# Sensors-V1.net
KiCad netlist of a schematic drawn in EAGLE
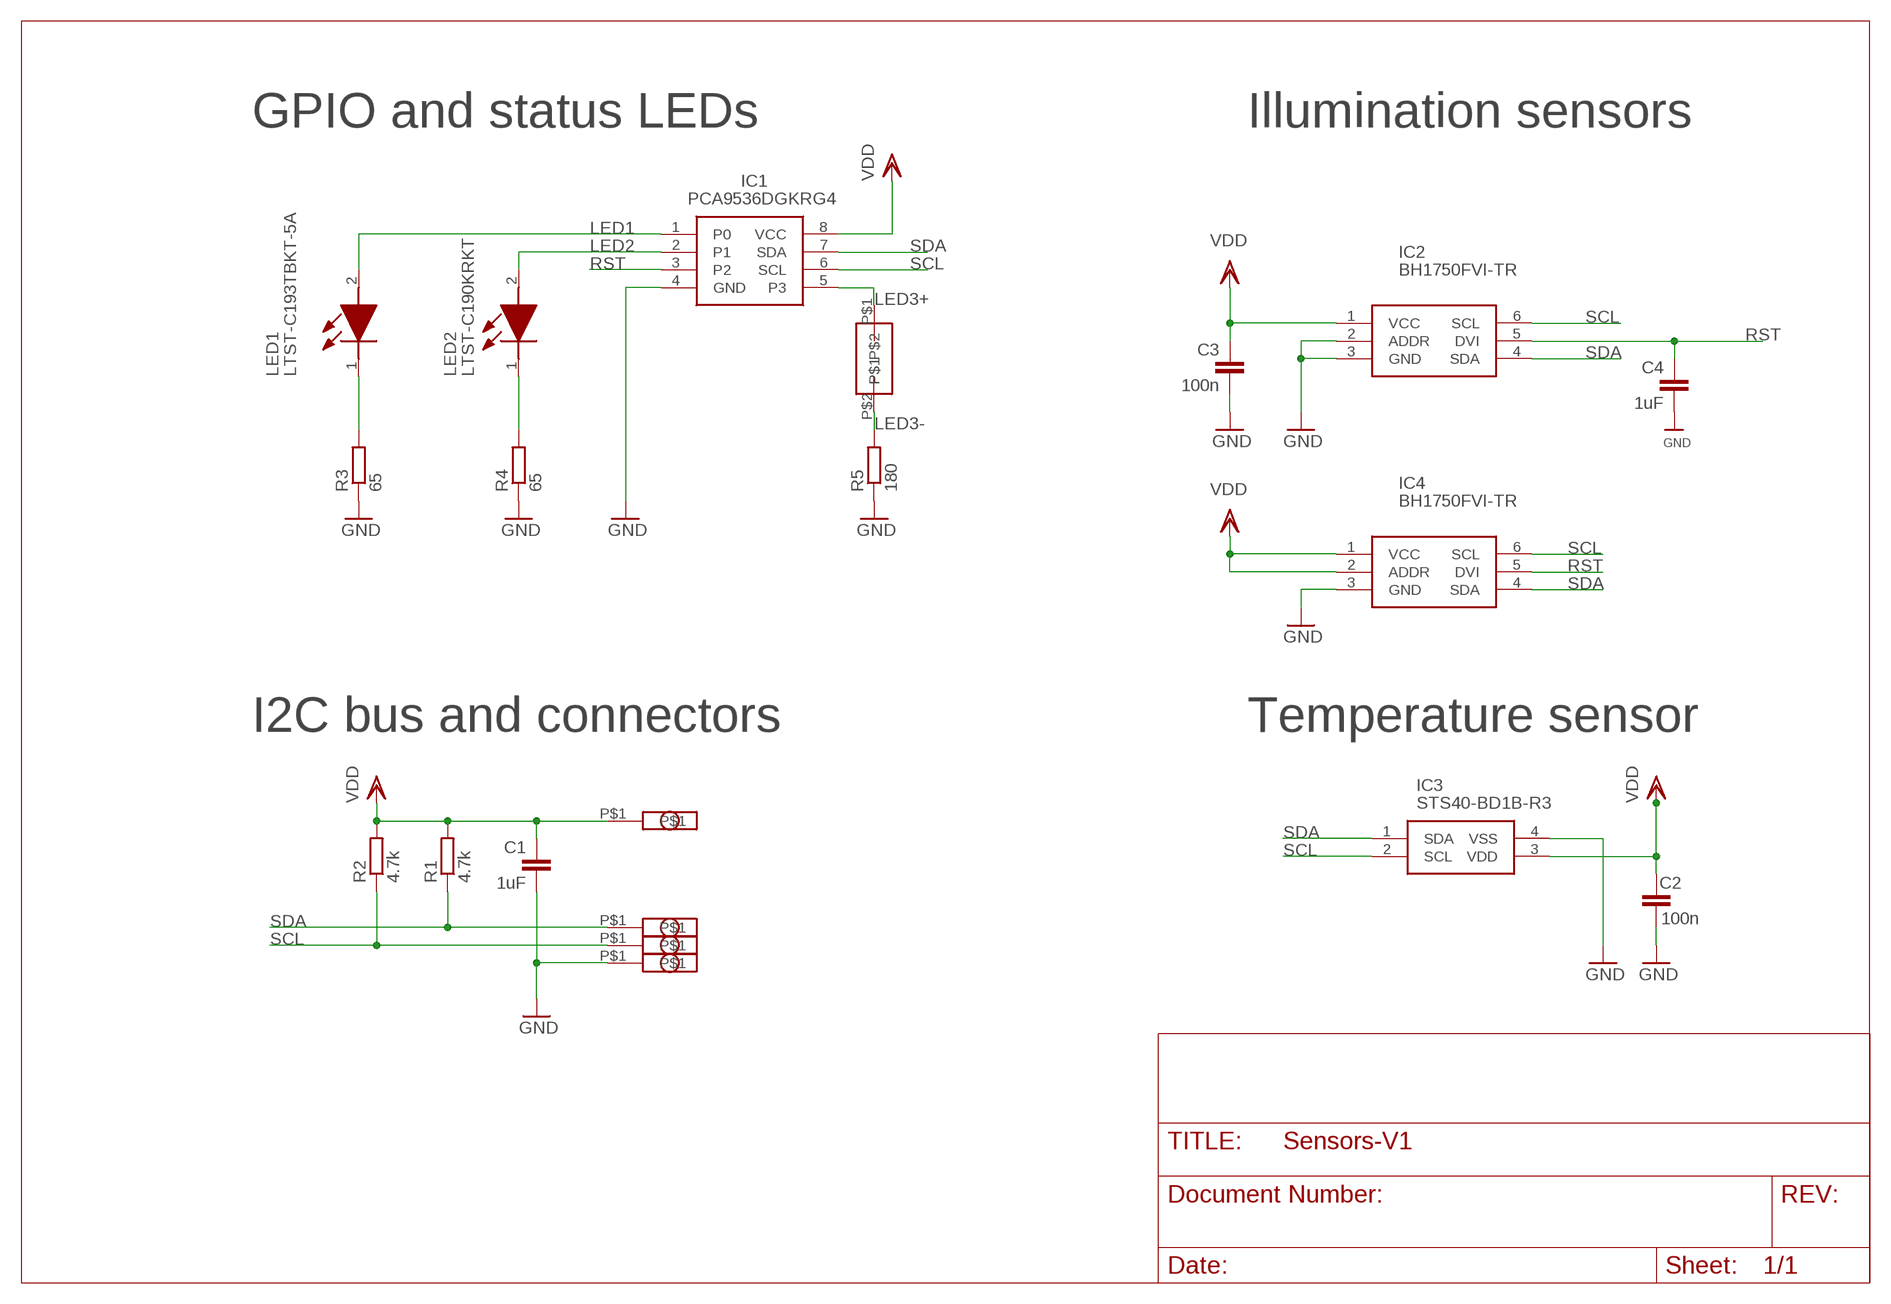
[diagram p0: schematic, sheet 1]

(export (version "E")
  (design (tool "Eeschema 10.0.6"))
  (components
    (comp (ref "C1")
      (value "1uF")
      (footprint "eagle-import:C0603")
      (libsource (lib "eagle-import") (part "C-EUC0603"))
    )
    (comp (ref "C2")
      (value "100n")
      (footprint "eagle-import:C0603")
      (libsource (lib "eagle-import") (part "C-EUC0603"))
    )
    (comp (ref "C3")
      (value "100n")
      (footprint "eagle-import:C0603")
      (libsource (lib "eagle-import") (part "C-EUC0603"))
    )
    (comp (ref "C4")
      (value "1uF")
      (footprint "eagle-import:C0603")
      (libsource (lib "eagle-import") (part "C-EUC0603"))
    )
    (comp (ref "IC1")
      (value "PCA9536DGKRG4")
      (footprint "eagle-import:SOP65P490X110-8N")
      (fields (field (name "MOUSER_PART_NUMBER") "595-PCA9536DGKRG4"))
      (libsource (lib "eagle-import") (part "PCA9536DGKRG4"))
    )
    (comp (ref "IC2")
      (value "BH1750FVI-TR")
      (footprint "eagle-import:WSOF6")
      (libsource (lib "eagle-import") (part "BH1750FVI-TR"))
    )
    (comp (ref "IC3")
      (value "STS40-BD1B-R3")
      (footprint "eagle-import:STS40BD1BR3")
      (fields (field (name "MOUSER_PART_NUMBER") "403-STS40-BD1B-R3"))
      (libsource (lib "eagle-import") (part "STS40-BD1B-R3"))
    )
    (comp (ref "IC4")
      (value "BH1750FVI-TR")
      (footprint "eagle-import:WSOF6")
      (libsource (lib "eagle-import") (part "BH1750FVI-TR"))
    )
    (comp (ref "LED1")
      (value "LTST-C193TBKT-5A")
      (footprint "eagle-import:LEDC1608X45N")
      (fields (field (name "MOUSER_PART_NUMBER") "859-LTSTC193TBKT5A"))
      (libsource (lib "eagle-import") (part "LTST-C193TBKT-5A"))
    )
    (comp (ref "LED2")
      (value "LTST-C190KRKT")
      (footprint "eagle-import:LEDC1607X80N")
      (fields
        (field (name "MANUFACTURER_PART_NUMBER") "LTST-C190KFKT")
        (field (name "MOUSER_PART_NUMBER") "859-LTST-C190KFKT")
      )
      (libsource (lib "eagle-import") (part "LTST-C190KFKT"))
    )
    (comp (ref "R1")
      (value "4.7k")
      (footprint "eagle-import:R0603")
      (libsource (lib "eagle-import") (part "R_JLMR0603"))
    )
    (comp (ref "R2")
      (value "4.7k")
      (footprint "eagle-import:R0603")
      (libsource (lib "eagle-import") (part "R_JLMR0603"))
    )
    (comp (ref "R3")
      (value "65")
      (footprint "eagle-import:R0603")
      (libsource (lib "eagle-import") (part "R_JLMR0603"))
    )
    (comp (ref "R4")
      (value "65")
      (footprint "eagle-import:R0603")
      (libsource (lib "eagle-import") (part "R_JLMR0603"))
    )
    (comp (ref "R5")
      (value "180")
      (footprint "eagle-import:R0603")
      (libsource (lib "eagle-import") (part "R_JLMR0603"))
    )
    (comp (ref "U$1")
      (value "PAD")
      (footprint "eagle-import:PAD-15")
      (libsource (lib "eagle-import") (part "PAD"))
    )
    (comp (ref "U$2")
      (value "PAD")
      (footprint "eagle-import:PAD-15")
      (libsource (lib "eagle-import") (part "PAD"))
    )
    (comp (ref "U$3")
      (value "PAD")
      (footprint "eagle-import:PAD-15")
      (libsource (lib "eagle-import") (part "PAD"))
    )
    (comp (ref "U$4")
      (value "PAD")
      (footprint "eagle-import:PAD-15")
      (libsource (lib "eagle-import") (part "PAD"))
    )
    (comp (ref "U$5")
      (value "LEDPINS")
      (footprint "eagle-import:LEDPINS254")
      (libsource (lib "eagle-import") (part "LEDPINS"))
    )
  )
  (nets
    (net (code "1") (name "/LED1") (class "Default")
      (node (ref "IC1") (pin "1") (pinfunction "P0_1") (pintype "bidirectional"))
      (node (ref "LED1") (pin "2") (pinfunction "A_2") (pintype "bidirectional"))
    )
    (net (code "2") (name "/LED2") (class "Default")
      (node (ref "IC1") (pin "2") (pinfunction "P1_2") (pintype "bidirectional"))
      (node (ref "LED2") (pin "2") (pinfunction "A_2") (pintype "bidirectional"))
    )
    (net (code "3") (name "/LED3+") (class "Default")
      (node (ref "IC1") (pin "5") (pinfunction "P3_5") (pintype "bidirectional"))
      (node (ref "U$5") (pin "P$1") (pinfunction "P$1_P$1") (pintype "bidirectional"))
    )
    (net (code "4") (name "/LED3-") (class "Default")
      (node (ref "R5") (pin "2") (pinfunction "2_2") (pintype "passive"))
      (node (ref "U$5") (pin "P$2") (pinfunction "P$2_P$2") (pintype "bidirectional"))
    )
    (net (code "5") (name "/RST") (class "Default")
      (node (ref "C4") (pin "1") (pinfunction "1_1") (pintype "passive"))
      (node (ref "IC1") (pin "3") (pinfunction "P2_3") (pintype "bidirectional"))
      (node (ref "IC2") (pin "5") (pinfunction "DVI_5") (pintype "bidirectional"))
      (node (ref "IC4") (pin "5") (pinfunction "DVI_5") (pintype "bidirectional"))
    )
    (net (code "6") (name "/SCL") (class "Default")
      (node (ref "IC1") (pin "6") (pinfunction "SCL_6") (pintype "bidirectional"))
      (node (ref "IC2") (pin "6") (pinfunction "SCL_6") (pintype "bidirectional"))
      (node (ref "IC3") (pin "2") (pinfunction "SCL_2") (pintype "bidirectional"))
      (node (ref "IC4") (pin "6") (pinfunction "SCL_6") (pintype "bidirectional"))
      (node (ref "R2") (pin "1") (pinfunction "1_1") (pintype "passive"))
      (node (ref "U$2") (pin "P$1") (pinfunction "P$1_P$1") (pintype "bidirectional"))
    )
    (net (code "7") (name "/SDA") (class "Default")
      (node (ref "IC1") (pin "7") (pinfunction "SDA_7") (pintype "bidirectional"))
      (node (ref "IC2") (pin "4") (pinfunction "SDA_4") (pintype "bidirectional"))
      (node (ref "IC3") (pin "1") (pinfunction "SDA_1") (pintype "bidirectional"))
      (node (ref "IC4") (pin "4") (pinfunction "SDA_4") (pintype "bidirectional"))
      (node (ref "R1") (pin "1") (pinfunction "1_1") (pintype "passive"))
      (node (ref "U$1") (pin "P$1") (pinfunction "P$1_P$1") (pintype "bidirectional"))
    )
    (net (code "8") (name "GND") (class "Default")
      (node (ref "C1") (pin "2") (pinfunction "2_2") (pintype "passive"))
      (node (ref "C2") (pin "2") (pinfunction "2_2") (pintype "passive"))
      (node (ref "C3") (pin "2") (pinfunction "2_2") (pintype "passive"))
      (node (ref "C4") (pin "2") (pinfunction "2_2") (pintype "passive"))
      (node (ref "IC1") (pin "4") (pinfunction "GND_4") (pintype "bidirectional"))
      (node (ref "IC2") (pin "2") (pinfunction "ADDR_2") (pintype "bidirectional"))
      (node (ref "IC2") (pin "3") (pinfunction "GND_3") (pintype "bidirectional"))
      (node (ref "IC3") (pin "4") (pinfunction "VSS_4") (pintype "bidirectional"))
      (node (ref "IC4") (pin "3") (pinfunction "GND_3") (pintype "bidirectional"))
      (node (ref "R3") (pin "1") (pinfunction "1_1") (pintype "passive"))
      (node (ref "R4") (pin "1") (pinfunction "1_1") (pintype "passive"))
      (node (ref "R5") (pin "1") (pinfunction "1_1") (pintype "passive"))
      (node (ref "U$3") (pin "P$1") (pinfunction "P$1_P$1") (pintype "bidirectional"))
    )
    (net (code "9") (name "Net-(LED1-K)") (class "Default")
      (node (ref "LED1") (pin "1") (pinfunction "K_1") (pintype "bidirectional"))
      (node (ref "R3") (pin "2") (pinfunction "2_2") (pintype "passive"))
    )
    (net (code "10") (name "Net-(LED2-K)") (class "Default")
      (node (ref "LED2") (pin "1") (pinfunction "K_1") (pintype "bidirectional"))
      (node (ref "R4") (pin "2") (pinfunction "2_2") (pintype "passive"))
    )
    (net (code "11") (name "VDD") (class "Default")
      (node (ref "C1") (pin "1") (pinfunction "1_1") (pintype "passive"))
      (node (ref "C2") (pin "1") (pinfunction "1_1") (pintype "passive"))
      (node (ref "C3") (pin "1") (pinfunction "1_1") (pintype "passive"))
      (node (ref "IC1") (pin "8") (pinfunction "VCC_8") (pintype "bidirectional"))
      (node (ref "IC2") (pin "1") (pinfunction "VCC_1") (pintype "bidirectional"))
      (node (ref "IC3") (pin "3") (pinfunction "VDD_3") (pintype "bidirectional"))
      (node (ref "IC4") (pin "1") (pinfunction "VCC_1") (pintype "bidirectional"))
      (node (ref "IC4") (pin "2") (pinfunction "ADDR_2") (pintype "bidirectional"))
      (node (ref "R1") (pin "2") (pinfunction "2_2") (pintype "passive"))
      (node (ref "R2") (pin "2") (pinfunction "2_2") (pintype "passive"))
      (node (ref "U$4") (pin "P$1") (pinfunction "P$1_P$1") (pintype "bidirectional"))
    )
  )
)
